# Sheet2.net
KiCad netlist of a schematic drawn in Altium Designer
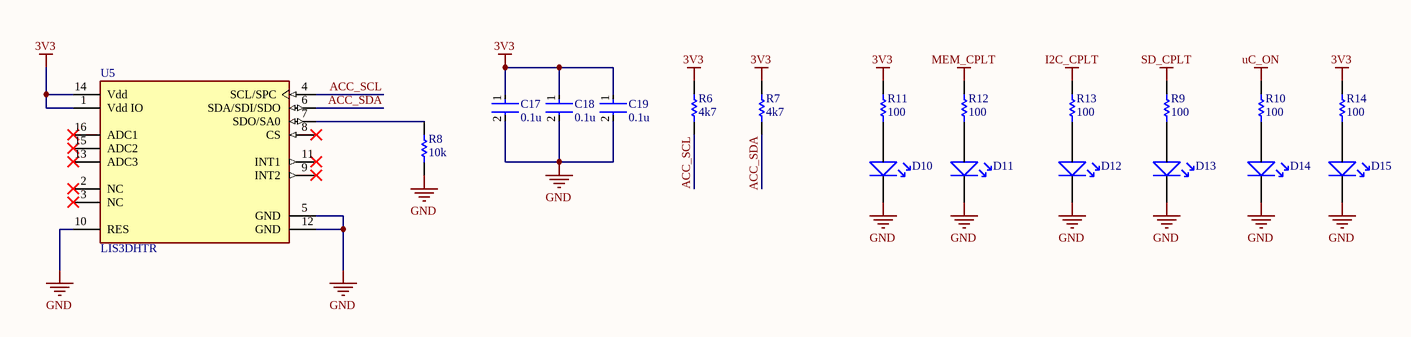
[diagram p0: Sheet2.SchDoc]

(export (version "E")
  (design (tool "Eeschema 10.0.6"))
  (components
    (comp (ref "C17")
      (value "0.1u")
      (footprint "FP-C0603C-CF-MFG")
      (description "CAP CER 0.1UF 50V X7R 0603")
      (fields (field (name "TOLERANCE") "0.1") (field (name "MANUFACTURER") "KEMET"))
      (libsource (lib "Altium Content Vault") (part "b4654b650e69147ec39a6b967a45e02"))
    )
    (comp (ref "C18")
      (value "0.1u")
      (footprint "FP-C0603C-CF-MFG")
      (description "CAP CER 0.1UF 50V X7R 0603")
      (fields (field (name "TOLERANCE") "0.1") (field (name "MANUFACTURER") "KEMET"))
      (libsource (lib "Altium Content Vault") (part "b4654b650e69147ec39a6b967a45e02"))
    )
    (comp (ref "C19")
      (value "0.1u")
      (footprint "FP-C0603C-CF-MFG")
      (description "CAP CER 0.1UF 50V X7R 0603")
      (fields (field (name "TOLERANCE") "0.1") (field (name "MANUFACTURER") "KEMET"))
      (libsource (lib "Altium Content Vault") (part "b4654b650e69147ec39a6b967a45e02"))
    )
    (comp (ref "D10")
      (value "0603 LED")
      (footprint "0603 LED")
      (libsource (lib "0603 LED") (part "0603 LED"))
    )
    (comp (ref "D11")
      (value "0603 LED")
      (footprint "0603 LED")
      (libsource (lib "0603 LED") (part "0603 LED"))
    )
    (comp (ref "D12")
      (value "0603 LED")
      (footprint "0603 LED")
      (libsource (lib "0603 LED") (part "0603 LED"))
    )
    (comp (ref "D13")
      (value "0603 LED")
      (footprint "0603 LED")
      (libsource (lib "0603 LED") (part "0603 LED"))
    )
    (comp (ref "D14")
      (value "0603 LED")
      (footprint "0603 LED")
      (libsource (lib "0603 LED") (part "0603 LED"))
    )
    (comp (ref "D15")
      (value "0603 LED")
      (footprint "0603 LED")
      (libsource (lib "0603 LED") (part "0603 LED"))
    )
    (comp (ref "R6")
      (value "4k7")
      (footprint "RESC1609X50X30NL8T20")
      (description "Chip Resistor, 10 KOhm, +/- 1%, 100 mW, -55 to 155 degC, 0603 (1608 Metric), RoHS, Tape and Reel")
      (fields (field (name "MANUFACTURER") "Vishay Semiconductor"))
      (libsource (lib "Altium Content Vault") (part "RES-2"))
    )
    (comp (ref "R7")
      (value "4k7")
      (footprint "RESC1609X50X30NL8T20")
      (description "Chip Resistor, 10 KOhm, +/- 1%, 100 mW, -55 to 155 degC, 0603 (1608 Metric), RoHS, Tape and Reel")
      (fields (field (name "MANUFACTURER") "Vishay Semiconductor"))
      (libsource (lib "Altium Content Vault") (part "RES-2"))
    )
    (comp (ref "R8")
      (value "10k")
      (footprint "RESC1609X50X30NL8T20")
      (description "Chip Resistor, 10 KOhm, +/- 1%, 100 mW, -55 to 155 degC, 0603 (1608 Metric), RoHS, Tape and Reel")
      (fields (field (name "MANUFACTURER") "Vishay Semiconductor"))
      (libsource (lib "Altium Content Vault") (part "RES-2"))
    )
    (comp (ref "R9")
      (value "100")
      (footprint "RESC1609X50X30NL8T20")
      (description "Chip Resistor, 10 KOhm, +/- 1%, 100 mW, -55 to 155 degC, 0603 (1608 Metric), RoHS, Tape and Reel")
      (fields (field (name "MANUFACTURER") "Vishay Semiconductor"))
      (libsource (lib "Altium Content Vault") (part "RES-2"))
    )
    (comp (ref "R10")
      (value "100")
      (footprint "RESC1609X50X30NL8T20")
      (description "Chip Resistor, 10 KOhm, +/- 1%, 100 mW, -55 to 155 degC, 0603 (1608 Metric), RoHS, Tape and Reel")
      (fields (field (name "MANUFACTURER") "Vishay Semiconductor"))
      (libsource (lib "Altium Content Vault") (part "RES-2"))
    )
    (comp (ref "R11")
      (value "100")
      (footprint "RESC1609X50X30NL8T20")
      (description "Chip Resistor, 10 KOhm, +/- 1%, 100 mW, -55 to 155 degC, 0603 (1608 Metric), RoHS, Tape and Reel")
      (fields (field (name "MANUFACTURER") "Vishay Semiconductor"))
      (libsource (lib "Altium Content Vault") (part "RES-2"))
    )
    (comp (ref "R12")
      (value "100")
      (footprint "RESC1609X50X30NL8T20")
      (description "Chip Resistor, 10 KOhm, +/- 1%, 100 mW, -55 to 155 degC, 0603 (1608 Metric), RoHS, Tape and Reel")
      (fields (field (name "MANUFACTURER") "Vishay Semiconductor"))
      (libsource (lib "Altium Content Vault") (part "RES-2"))
    )
    (comp (ref "R13")
      (value "100")
      (footprint "RESC1609X50X30NL8T20")
      (description "Chip Resistor, 10 KOhm, +/- 1%, 100 mW, -55 to 155 degC, 0603 (1608 Metric), RoHS, Tape and Reel")
      (fields (field (name "MANUFACTURER") "Vishay Semiconductor"))
      (libsource (lib "Altium Content Vault") (part "RES-2"))
    )
    (comp (ref "R14")
      (value "100")
      (footprint "RESC1609X50X30NL8T20")
      (description "Chip Resistor, 10 KOhm, +/- 1%, 100 mW, -55 to 155 degC, 0603 (1608 Metric), RoHS, Tape and Reel")
      (fields (field (name "MANUFACTURER") "Vishay Semiconductor"))
      (libsource (lib "Altium Content Vault") (part "RES-2"))
    )
    (comp (ref "U5")
      (value "LIS3DHTR")
      (footprint "FP-LGA-16-7983231-MFG")
      (description "ACCEL 2-16G I2C/SPI 16LGA")
      (libsource (lib "Altium Content Vault") (part "1e4772b22d749da4b53766bc623c8dd"))
    )
  )
  (nets
    (net (code "1") (name "/ACC_SCL") (class "Default")
      (node (ref "R6") (pin "1") (pinfunction "1_1") (pintype "passive"))
      (node (ref "U5") (pin "4") (pinfunction "SCL/SPC_4") (pintype "input"))
    )
    (net (code "2") (name "/ACC_SDA") (class "Default")
      (node (ref "R7") (pin "1") (pinfunction "1_1") (pintype "passive"))
      (node (ref "U5") (pin "6") (pinfunction "SDA/SDI/SDO_6") (pintype "bidirectional"))
    )
    (net (code "3") (name "3V3") (class "Default")
      (node (ref "C17") (pin "1") (pinfunction "1_1") (pintype "passive"))
      (node (ref "C18") (pin "1") (pinfunction "1_1") (pintype "passive"))
      (node (ref "C19") (pin "1") (pinfunction "1_1") (pintype "passive"))
      (node (ref "R11") (pin "2") (pinfunction "2_2") (pintype "passive"))
      (node (ref "R14") (pin "2") (pinfunction "2_2") (pintype "passive"))
      (node (ref "R6") (pin "2") (pinfunction "2_2") (pintype "passive"))
      (node (ref "R7") (pin "2") (pinfunction "2_2") (pintype "passive"))
      (node (ref "U5") (pin "1") (pinfunction "Vdd_IO_1") (pintype "power_in"))
      (node (ref "U5") (pin "14") (pinfunction "Vdd_14") (pintype "power_in"))
    )
    (net (code "4") (name "GND") (class "Default")
      (node (ref "C17") (pin "2") (pinfunction "2_2") (pintype "passive"))
      (node (ref "C18") (pin "2") (pinfunction "2_2") (pintype "passive"))
      (node (ref "C19") (pin "2") (pinfunction "2_2") (pintype "passive"))
      (node (ref "D10") (pin "2") (pinfunction "5_2") (pintype "passive"))
      (node (ref "D11") (pin "2") (pinfunction "5_2") (pintype "passive"))
      (node (ref "D12") (pin "2") (pinfunction "5_2") (pintype "passive"))
      (node (ref "D13") (pin "2") (pinfunction "5_2") (pintype "passive"))
      (node (ref "D14") (pin "2") (pinfunction "5_2") (pintype "passive"))
      (node (ref "D15") (pin "2") (pinfunction "5_2") (pintype "passive"))
      (node (ref "R8") (pin "1") (pinfunction "1_1") (pintype "passive"))
      (node (ref "U5") (pin "10") (pinfunction "RES_10") (pintype "passive"))
      (node (ref "U5") (pin "12") (pinfunction "GND_12") (pintype "power_in"))
      (node (ref "U5") (pin "5") (pinfunction "GND_5") (pintype "power_in"))
    )
    (net (code "5") (name "I2C_CPLT") (class "Default")
      (node (ref "R13") (pin "2") (pinfunction "2_2") (pintype "passive"))
    )
    (net (code "6") (name "MEM_CPLT") (class "Default")
      (node (ref "R12") (pin "2") (pinfunction "2_2") (pintype "passive"))
    )
    (net (code "7") (name "Net-(D10-6)") (class "Default")
      (node (ref "D10") (pin "1") (pinfunction "6_1") (pintype "passive"))
      (node (ref "R11") (pin "1") (pinfunction "1_1") (pintype "passive"))
    )
    (net (code "8") (name "Net-(D11-6)") (class "Default")
      (node (ref "D11") (pin "1") (pinfunction "6_1") (pintype "passive"))
      (node (ref "R12") (pin "1") (pinfunction "1_1") (pintype "passive"))
    )
    (net (code "9") (name "Net-(D12-6)") (class "Default")
      (node (ref "D12") (pin "1") (pinfunction "6_1") (pintype "passive"))
      (node (ref "R13") (pin "1") (pinfunction "1_1") (pintype "passive"))
    )
    (net (code "10") (name "Net-(D13-6)") (class "Default")
      (node (ref "D13") (pin "1") (pinfunction "6_1") (pintype "passive"))
      (node (ref "R9") (pin "1") (pinfunction "1_1") (pintype "passive"))
    )
    (net (code "11") (name "Net-(D14-6)") (class "Default")
      (node (ref "D14") (pin "1") (pinfunction "6_1") (pintype "passive"))
      (node (ref "R10") (pin "1") (pinfunction "1_1") (pintype "passive"))
    )
    (net (code "12") (name "Net-(D15-6)") (class "Default")
      (node (ref "D15") (pin "1") (pinfunction "6_1") (pintype "passive"))
      (node (ref "R14") (pin "1") (pinfunction "1_1") (pintype "passive"))
    )
    (net (code "13") (name "Net-(U5-SDO{slash}SA0)") (class "Default")
      (node (ref "R8") (pin "2") (pinfunction "2_2") (pintype "passive"))
      (node (ref "U5") (pin "7") (pinfunction "SDO/SA0_7") (pintype "bidirectional"))
    )
    (net (code "14") (name "SD_CPLT") (class "Default")
      (node (ref "R9") (pin "2") (pinfunction "2_2") (pintype "passive"))
    )
    (net (code "15") (name "uC_ON") (class "Default")
      (node (ref "R10") (pin "2") (pinfunction "2_2") (pintype "passive"))
    )
    (net (code "16") (name "unconnected-(U5-ADC1-Pad16)") (class "Default")
      (node (ref "U5") (pin "16") (pinfunction "ADC1_16") (pintype "passive+no_connect"))
    )
    (net (code "17") (name "unconnected-(U5-ADC2-Pad15)") (class "Default")
      (node (ref "U5") (pin "15") (pinfunction "ADC2_15") (pintype "passive+no_connect"))
    )
    (net (code "18") (name "unconnected-(U5-ADC3-Pad13)") (class "Default")
      (node (ref "U5") (pin "13") (pinfunction "ADC3_13") (pintype "passive+no_connect"))
    )
    (net (code "19") (name "unconnected-(U5-CS-Pad8)") (class "Default")
      (node (ref "U5") (pin "8") (pinfunction "CS_8") (pintype "input+no_connect"))
    )
    (net (code "20") (name "unconnected-(U5-INT1-Pad11)") (class "Default")
      (node (ref "U5") (pin "11") (pinfunction "INT1_11") (pintype "output+no_connect"))
    )
    (net (code "21") (name "unconnected-(U5-INT2-Pad9)") (class "Default")
      (node (ref "U5") (pin "9") (pinfunction "INT2_9") (pintype "output+no_connect"))
    )
    (net (code "22") (name "unconnected-(U5-NC-Pad2)") (class "Default")
      (node (ref "U5") (pin "2") (pinfunction "NC_2") (pintype "passive+no_connect"))
    )
    (net (code "23") (name "unconnected-(U5-NC-Pad3)") (class "Default")
      (node (ref "U5") (pin "3") (pinfunction "NC_3") (pintype "passive+no_connect"))
    )
  )
)
